# mother.net
KiCad netlist of a schematic drawn in EAGLE
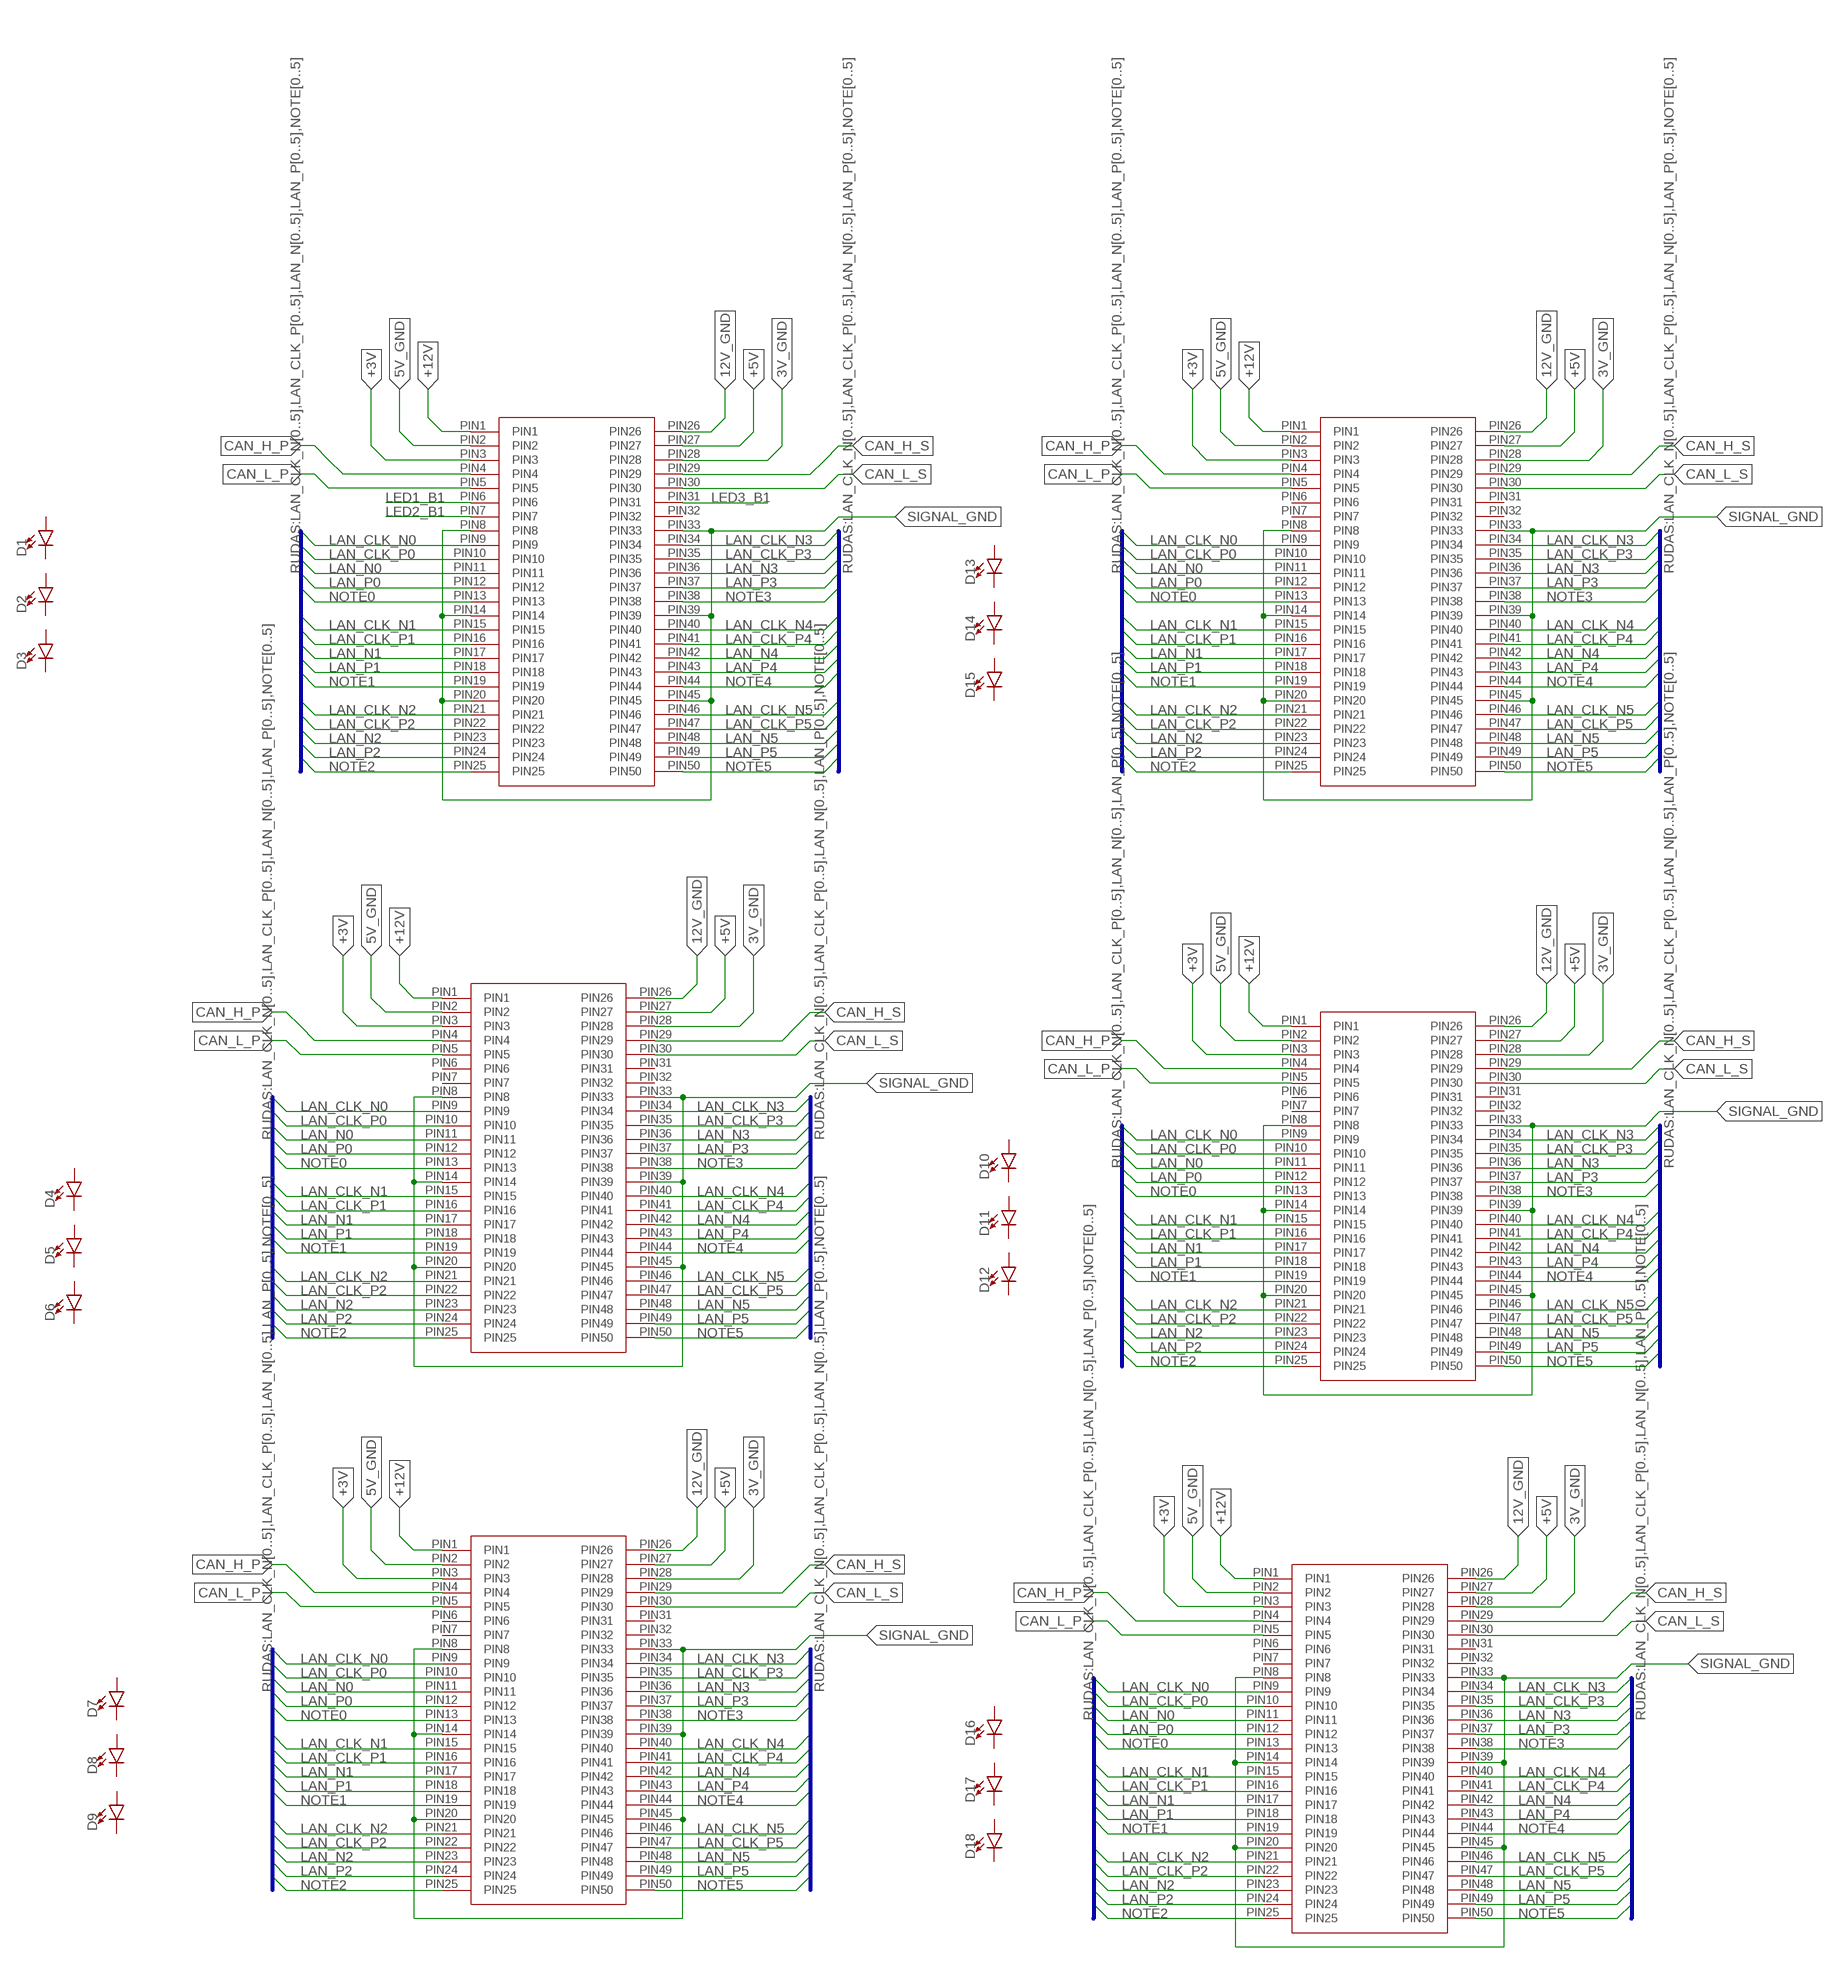
[diagram p0: schematic, sheet 1]

(export (version "E")
  (design (tool "Eeschema 10.0.6"))
  (components
    (comp (ref "D1")
      (value "LED-FKIT-1206")
      (footprint "eagle-import:FKIT-LED-1206")
      (libsource (lib "eagle-import") (part "LED-FKIT-1206"))
    )
    (comp (ref "D2")
      (value "LED-FKIT-1206")
      (footprint "eagle-import:FKIT-LED-1206")
      (libsource (lib "eagle-import") (part "LED-FKIT-1206"))
    )
    (comp (ref "D3")
      (value "LED-FKIT-1206")
      (footprint "eagle-import:FKIT-LED-1206")
      (libsource (lib "eagle-import") (part "LED-FKIT-1206"))
    )
    (comp (ref "D4")
      (value "LED-FKIT-1206")
      (footprint "eagle-import:FKIT-LED-1206")
      (libsource (lib "eagle-import") (part "LED-FKIT-1206"))
    )
    (comp (ref "D5")
      (value "LED-FKIT-1206")
      (footprint "eagle-import:FKIT-LED-1206")
      (libsource (lib "eagle-import") (part "LED-FKIT-1206"))
    )
    (comp (ref "D6")
      (value "LED-FKIT-1206")
      (footprint "eagle-import:FKIT-LED-1206")
      (libsource (lib "eagle-import") (part "LED-FKIT-1206"))
    )
    (comp (ref "D7")
      (value "LED-FKIT-1206")
      (footprint "eagle-import:FKIT-LED-1206")
      (libsource (lib "eagle-import") (part "LED-FKIT-1206"))
    )
    (comp (ref "D8")
      (value "LED-FKIT-1206")
      (footprint "eagle-import:FKIT-LED-1206")
      (libsource (lib "eagle-import") (part "LED-FKIT-1206"))
    )
    (comp (ref "D9")
      (value "LED-FKIT-1206")
      (footprint "eagle-import:FKIT-LED-1206")
      (libsource (lib "eagle-import") (part "LED-FKIT-1206"))
    )
    (comp (ref "D10")
      (value "LED-FKIT-1206")
      (footprint "eagle-import:FKIT-LED-1206")
      (libsource (lib "eagle-import") (part "LED-FKIT-1206"))
    )
    (comp (ref "D11")
      (value "LED-FKIT-1206")
      (footprint "eagle-import:FKIT-LED-1206")
      (libsource (lib "eagle-import") (part "LED-FKIT-1206"))
    )
    (comp (ref "D12")
      (value "LED-FKIT-1206")
      (footprint "eagle-import:FKIT-LED-1206")
      (libsource (lib "eagle-import") (part "LED-FKIT-1206"))
    )
    (comp (ref "D13")
      (value "LED-FKIT-1206")
      (footprint "eagle-import:FKIT-LED-1206")
      (libsource (lib "eagle-import") (part "LED-FKIT-1206"))
    )
    (comp (ref "D14")
      (value "LED-FKIT-1206")
      (footprint "eagle-import:FKIT-LED-1206")
      (libsource (lib "eagle-import") (part "LED-FKIT-1206"))
    )
    (comp (ref "D15")
      (value "LED-FKIT-1206")
      (footprint "eagle-import:FKIT-LED-1206")
      (libsource (lib "eagle-import") (part "LED-FKIT-1206"))
    )
    (comp (ref "D16")
      (value "LED-FKIT-1206")
      (footprint "eagle-import:FKIT-LED-1206")
      (libsource (lib "eagle-import") (part "LED-FKIT-1206"))
    )
    (comp (ref "D17")
      (value "LED-FKIT-1206")
      (footprint "eagle-import:FKIT-LED-1206")
      (libsource (lib "eagle-import") (part "LED-FKIT-1206"))
    )
    (comp (ref "D18")
      (value "LED-FKIT-1206")
      (footprint "eagle-import:FKIT-LED-1206")
      (libsource (lib "eagle-import") (part "LED-FKIT-1206"))
    )
    (comp (ref "U$1")
      (value "CARD_EDGE_50PINM80-4115042")
      (footprint "eagle-import:M80-4115042")
      (libsource (lib "eagle-import") (part "CARD_EDGE_50PINM80-4115042"))
    )
    (comp (ref "U$2")
      (value "CARD_EDGE_50PINM80-4115042")
      (footprint "eagle-import:M80-4115042")
      (libsource (lib "eagle-import") (part "CARD_EDGE_50PINM80-4115042"))
    )
    (comp (ref "U$3")
      (value "CARD_EDGE_50PINM80-4115042")
      (footprint "eagle-import:M80-4115042")
      (libsource (lib "eagle-import") (part "CARD_EDGE_50PINM80-4115042"))
    )
    (comp (ref "U$4")
      (value "CARD_EDGE_50PINM80-4115042")
      (footprint "eagle-import:M80-4115042")
      (libsource (lib "eagle-import") (part "CARD_EDGE_50PINM80-4115042"))
    )
    (comp (ref "U$5")
      (value "CARD_EDGE_50PINM80-4115042")
      (footprint "eagle-import:M80-4115042")
      (libsource (lib "eagle-import") (part "CARD_EDGE_50PINM80-4115042"))
    )
    (comp (ref "U$6")
      (value "CARD_EDGE_50PINM80-4115042")
      (footprint "eagle-import:M80-4115042")
      (libsource (lib "eagle-import") (part "CARD_EDGE_50PINM80-4115042"))
    )
  )
  (nets
    (net (code "1") (name "+3V") (class "Default")
      (node (ref "U$1") (pin "PIN3") (pinfunction "PIN3_PIN3") (pintype "bidirectional"))
      (node (ref "U$2") (pin "PIN3") (pinfunction "PIN3_PIN3") (pintype "bidirectional"))
      (node (ref "U$3") (pin "PIN3") (pinfunction "PIN3_PIN3") (pintype "bidirectional"))
      (node (ref "U$4") (pin "PIN3") (pinfunction "PIN3_PIN3") (pintype "bidirectional"))
      (node (ref "U$5") (pin "PIN3") (pinfunction "PIN3_PIN3") (pintype "bidirectional"))
      (node (ref "U$6") (pin "PIN3") (pinfunction "PIN3_PIN3") (pintype "bidirectional"))
    )
    (net (code "2") (name "+5V") (class "Default")
      (node (ref "U$1") (pin "PIN27") (pinfunction "PIN27_PIN27") (pintype "bidirectional"))
      (node (ref "U$2") (pin "PIN27") (pinfunction "PIN27_PIN27") (pintype "bidirectional"))
      (node (ref "U$3") (pin "PIN27") (pinfunction "PIN27_PIN27") (pintype "bidirectional"))
      (node (ref "U$4") (pin "PIN27") (pinfunction "PIN27_PIN27") (pintype "bidirectional"))
      (node (ref "U$5") (pin "PIN27") (pinfunction "PIN27_PIN27") (pintype "bidirectional"))
      (node (ref "U$6") (pin "PIN27") (pinfunction "PIN27_PIN27") (pintype "bidirectional"))
    )
    (net (code "3") (name "+12V") (class "Default")
      (node (ref "U$1") (pin "PIN1") (pinfunction "PIN1_PIN1") (pintype "bidirectional"))
      (node (ref "U$2") (pin "PIN1") (pinfunction "PIN1_PIN1") (pintype "bidirectional"))
      (node (ref "U$3") (pin "PIN1") (pinfunction "PIN1_PIN1") (pintype "bidirectional"))
      (node (ref "U$4") (pin "PIN1") (pinfunction "PIN1_PIN1") (pintype "bidirectional"))
      (node (ref "U$5") (pin "PIN1") (pinfunction "PIN1_PIN1") (pintype "bidirectional"))
      (node (ref "U$6") (pin "PIN1") (pinfunction "PIN1_PIN1") (pintype "bidirectional"))
    )
    (net (code "4") (name "/LAN_CLK_N0") (class "Default")
      (node (ref "U$1") (pin "PIN9") (pinfunction "PIN9_PIN9") (pintype "bidirectional"))
      (node (ref "U$2") (pin "PIN9") (pinfunction "PIN9_PIN9") (pintype "bidirectional"))
      (node (ref "U$3") (pin "PIN9") (pinfunction "PIN9_PIN9") (pintype "bidirectional"))
      (node (ref "U$4") (pin "PIN9") (pinfunction "PIN9_PIN9") (pintype "bidirectional"))
      (node (ref "U$5") (pin "PIN9") (pinfunction "PIN9_PIN9") (pintype "bidirectional"))
      (node (ref "U$6") (pin "PIN9") (pinfunction "PIN9_PIN9") (pintype "bidirectional"))
    )
    (net (code "5") (name "/LAN_CLK_N1") (class "Default")
      (node (ref "U$1") (pin "PIN15") (pinfunction "PIN15_PIN15") (pintype "bidirectional"))
      (node (ref "U$2") (pin "PIN15") (pinfunction "PIN15_PIN15") (pintype "bidirectional"))
      (node (ref "U$3") (pin "PIN15") (pinfunction "PIN15_PIN15") (pintype "bidirectional"))
      (node (ref "U$4") (pin "PIN15") (pinfunction "PIN15_PIN15") (pintype "bidirectional"))
      (node (ref "U$5") (pin "PIN15") (pinfunction "PIN15_PIN15") (pintype "bidirectional"))
      (node (ref "U$6") (pin "PIN15") (pinfunction "PIN15_PIN15") (pintype "bidirectional"))
    )
    (net (code "6") (name "/LAN_CLK_N2") (class "Default")
      (node (ref "U$1") (pin "PIN21") (pinfunction "PIN21_PIN21") (pintype "bidirectional"))
      (node (ref "U$2") (pin "PIN21") (pinfunction "PIN21_PIN21") (pintype "bidirectional"))
      (node (ref "U$3") (pin "PIN21") (pinfunction "PIN21_PIN21") (pintype "bidirectional"))
      (node (ref "U$4") (pin "PIN21") (pinfunction "PIN21_PIN21") (pintype "bidirectional"))
      (node (ref "U$5") (pin "PIN21") (pinfunction "PIN21_PIN21") (pintype "bidirectional"))
      (node (ref "U$6") (pin "PIN21") (pinfunction "PIN21_PIN21") (pintype "bidirectional"))
    )
    (net (code "7") (name "/LAN_CLK_N3") (class "Default")
      (node (ref "U$1") (pin "PIN34") (pinfunction "PIN34_PIN34") (pintype "bidirectional"))
      (node (ref "U$2") (pin "PIN34") (pinfunction "PIN34_PIN34") (pintype "bidirectional"))
      (node (ref "U$3") (pin "PIN34") (pinfunction "PIN34_PIN34") (pintype "bidirectional"))
      (node (ref "U$4") (pin "PIN34") (pinfunction "PIN34_PIN34") (pintype "bidirectional"))
      (node (ref "U$5") (pin "PIN34") (pinfunction "PIN34_PIN34") (pintype "bidirectional"))
      (node (ref "U$6") (pin "PIN34") (pinfunction "PIN34_PIN34") (pintype "bidirectional"))
    )
    (net (code "8") (name "/LAN_CLK_N4") (class "Default")
      (node (ref "U$1") (pin "PIN40") (pinfunction "PIN40_PIN40") (pintype "bidirectional"))
      (node (ref "U$2") (pin "PIN40") (pinfunction "PIN40_PIN40") (pintype "bidirectional"))
      (node (ref "U$3") (pin "PIN40") (pinfunction "PIN40_PIN40") (pintype "bidirectional"))
      (node (ref "U$4") (pin "PIN40") (pinfunction "PIN40_PIN40") (pintype "bidirectional"))
      (node (ref "U$5") (pin "PIN40") (pinfunction "PIN40_PIN40") (pintype "bidirectional"))
      (node (ref "U$6") (pin "PIN40") (pinfunction "PIN40_PIN40") (pintype "bidirectional"))
    )
    (net (code "9") (name "/LAN_CLK_N5") (class "Default")
      (node (ref "U$1") (pin "PIN46") (pinfunction "PIN46_PIN46") (pintype "bidirectional"))
      (node (ref "U$2") (pin "PIN46") (pinfunction "PIN46_PIN46") (pintype "bidirectional"))
      (node (ref "U$3") (pin "PIN46") (pinfunction "PIN46_PIN46") (pintype "bidirectional"))
      (node (ref "U$4") (pin "PIN46") (pinfunction "PIN46_PIN46") (pintype "bidirectional"))
      (node (ref "U$5") (pin "PIN46") (pinfunction "PIN46_PIN46") (pintype "bidirectional"))
      (node (ref "U$6") (pin "PIN46") (pinfunction "PIN46_PIN46") (pintype "bidirectional"))
    )
    (net (code "10") (name "/LAN_CLK_P0") (class "Default")
      (node (ref "U$1") (pin "PIN10") (pinfunction "PIN10_PIN10") (pintype "bidirectional"))
      (node (ref "U$2") (pin "PIN10") (pinfunction "PIN10_PIN10") (pintype "bidirectional"))
      (node (ref "U$3") (pin "PIN10") (pinfunction "PIN10_PIN10") (pintype "bidirectional"))
      (node (ref "U$4") (pin "PIN10") (pinfunction "PIN10_PIN10") (pintype "bidirectional"))
      (node (ref "U$5") (pin "PIN10") (pinfunction "PIN10_PIN10") (pintype "bidirectional"))
      (node (ref "U$6") (pin "PIN10") (pinfunction "PIN10_PIN10") (pintype "bidirectional"))
    )
    (net (code "11") (name "/LAN_CLK_P1") (class "Default")
      (node (ref "U$1") (pin "PIN16") (pinfunction "PIN16_PIN16") (pintype "bidirectional"))
      (node (ref "U$2") (pin "PIN16") (pinfunction "PIN16_PIN16") (pintype "bidirectional"))
      (node (ref "U$3") (pin "PIN16") (pinfunction "PIN16_PIN16") (pintype "bidirectional"))
      (node (ref "U$4") (pin "PIN16") (pinfunction "PIN16_PIN16") (pintype "bidirectional"))
      (node (ref "U$5") (pin "PIN16") (pinfunction "PIN16_PIN16") (pintype "bidirectional"))
      (node (ref "U$6") (pin "PIN16") (pinfunction "PIN16_PIN16") (pintype "bidirectional"))
    )
    (net (code "12") (name "/LAN_CLK_P2") (class "Default")
      (node (ref "U$1") (pin "PIN22") (pinfunction "PIN22_PIN22") (pintype "bidirectional"))
      (node (ref "U$2") (pin "PIN22") (pinfunction "PIN22_PIN22") (pintype "bidirectional"))
      (node (ref "U$3") (pin "PIN22") (pinfunction "PIN22_PIN22") (pintype "bidirectional"))
      (node (ref "U$4") (pin "PIN22") (pinfunction "PIN22_PIN22") (pintype "bidirectional"))
      (node (ref "U$5") (pin "PIN22") (pinfunction "PIN22_PIN22") (pintype "bidirectional"))
      (node (ref "U$6") (pin "PIN22") (pinfunction "PIN22_PIN22") (pintype "bidirectional"))
    )
    (net (code "13") (name "/LAN_CLK_P3") (class "Default")
      (node (ref "U$1") (pin "PIN35") (pinfunction "PIN35_PIN35") (pintype "bidirectional"))
      (node (ref "U$2") (pin "PIN35") (pinfunction "PIN35_PIN35") (pintype "bidirectional"))
      (node (ref "U$3") (pin "PIN35") (pinfunction "PIN35_PIN35") (pintype "bidirectional"))
      (node (ref "U$4") (pin "PIN35") (pinfunction "PIN35_PIN35") (pintype "bidirectional"))
      (node (ref "U$5") (pin "PIN35") (pinfunction "PIN35_PIN35") (pintype "bidirectional"))
      (node (ref "U$6") (pin "PIN35") (pinfunction "PIN35_PIN35") (pintype "bidirectional"))
    )
    (net (code "14") (name "/LAN_CLK_P4") (class "Default")
      (node (ref "U$1") (pin "PIN41") (pinfunction "PIN41_PIN41") (pintype "bidirectional"))
      (node (ref "U$2") (pin "PIN41") (pinfunction "PIN41_PIN41") (pintype "bidirectional"))
      (node (ref "U$3") (pin "PIN41") (pinfunction "PIN41_PIN41") (pintype "bidirectional"))
      (node (ref "U$4") (pin "PIN41") (pinfunction "PIN41_PIN41") (pintype "bidirectional"))
      (node (ref "U$5") (pin "PIN41") (pinfunction "PIN41_PIN41") (pintype "bidirectional"))
      (node (ref "U$6") (pin "PIN41") (pinfunction "PIN41_PIN41") (pintype "bidirectional"))
    )
    (net (code "15") (name "/LAN_CLK_P5") (class "Default")
      (node (ref "U$1") (pin "PIN47") (pinfunction "PIN47_PIN47") (pintype "bidirectional"))
      (node (ref "U$2") (pin "PIN47") (pinfunction "PIN47_PIN47") (pintype "bidirectional"))
      (node (ref "U$3") (pin "PIN47") (pinfunction "PIN47_PIN47") (pintype "bidirectional"))
      (node (ref "U$4") (pin "PIN47") (pinfunction "PIN47_PIN47") (pintype "bidirectional"))
      (node (ref "U$5") (pin "PIN47") (pinfunction "PIN47_PIN47") (pintype "bidirectional"))
      (node (ref "U$6") (pin "PIN47") (pinfunction "PIN47_PIN47") (pintype "bidirectional"))
    )
    (net (code "16") (name "/LAN_N0") (class "Default")
      (node (ref "U$1") (pin "PIN11") (pinfunction "PIN11_PIN11") (pintype "bidirectional"))
      (node (ref "U$2") (pin "PIN11") (pinfunction "PIN11_PIN11") (pintype "bidirectional"))
      (node (ref "U$3") (pin "PIN11") (pinfunction "PIN11_PIN11") (pintype "bidirectional"))
      (node (ref "U$4") (pin "PIN11") (pinfunction "PIN11_PIN11") (pintype "bidirectional"))
      (node (ref "U$5") (pin "PIN11") (pinfunction "PIN11_PIN11") (pintype "bidirectional"))
      (node (ref "U$6") (pin "PIN11") (pinfunction "PIN11_PIN11") (pintype "bidirectional"))
    )
    (net (code "17") (name "/LAN_N1") (class "Default")
      (node (ref "U$1") (pin "PIN17") (pinfunction "PIN17_PIN17") (pintype "bidirectional"))
      (node (ref "U$2") (pin "PIN17") (pinfunction "PIN17_PIN17") (pintype "bidirectional"))
      (node (ref "U$3") (pin "PIN17") (pinfunction "PIN17_PIN17") (pintype "bidirectional"))
      (node (ref "U$4") (pin "PIN17") (pinfunction "PIN17_PIN17") (pintype "bidirectional"))
      (node (ref "U$5") (pin "PIN17") (pinfunction "PIN17_PIN17") (pintype "bidirectional"))
      (node (ref "U$6") (pin "PIN17") (pinfunction "PIN17_PIN17") (pintype "bidirectional"))
    )
    (net (code "18") (name "/LAN_N2") (class "Default")
      (node (ref "U$1") (pin "PIN23") (pinfunction "PIN23_PIN23") (pintype "bidirectional"))
      (node (ref "U$2") (pin "PIN23") (pinfunction "PIN23_PIN23") (pintype "bidirectional"))
      (node (ref "U$3") (pin "PIN23") (pinfunction "PIN23_PIN23") (pintype "bidirectional"))
      (node (ref "U$4") (pin "PIN23") (pinfunction "PIN23_PIN23") (pintype "bidirectional"))
      (node (ref "U$5") (pin "PIN23") (pinfunction "PIN23_PIN23") (pintype "bidirectional"))
      (node (ref "U$6") (pin "PIN23") (pinfunction "PIN23_PIN23") (pintype "bidirectional"))
    )
    (net (code "19") (name "/LAN_N3") (class "Default")
      (node (ref "U$1") (pin "PIN36") (pinfunction "PIN36_PIN36") (pintype "bidirectional"))
      (node (ref "U$2") (pin "PIN36") (pinfunction "PIN36_PIN36") (pintype "bidirectional"))
      (node (ref "U$3") (pin "PIN36") (pinfunction "PIN36_PIN36") (pintype "bidirectional"))
      (node (ref "U$4") (pin "PIN36") (pinfunction "PIN36_PIN36") (pintype "bidirectional"))
      (node (ref "U$5") (pin "PIN36") (pinfunction "PIN36_PIN36") (pintype "bidirectional"))
      (node (ref "U$6") (pin "PIN36") (pinfunction "PIN36_PIN36") (pintype "bidirectional"))
    )
    (net (code "20") (name "/LAN_N4") (class "Default")
      (node (ref "U$1") (pin "PIN42") (pinfunction "PIN42_PIN42") (pintype "bidirectional"))
      (node (ref "U$2") (pin "PIN42") (pinfunction "PIN42_PIN42") (pintype "bidirectional"))
      (node (ref "U$3") (pin "PIN42") (pinfunction "PIN42_PIN42") (pintype "bidirectional"))
      (node (ref "U$4") (pin "PIN42") (pinfunction "PIN42_PIN42") (pintype "bidirectional"))
      (node (ref "U$5") (pin "PIN42") (pinfunction "PIN42_PIN42") (pintype "bidirectional"))
      (node (ref "U$6") (pin "PIN42") (pinfunction "PIN42_PIN42") (pintype "bidirectional"))
    )
    (net (code "21") (name "/LAN_N5") (class "Default")
      (node (ref "U$1") (pin "PIN48") (pinfunction "PIN48_PIN48") (pintype "bidirectional"))
      (node (ref "U$2") (pin "PIN48") (pinfunction "PIN48_PIN48") (pintype "bidirectional"))
      (node (ref "U$3") (pin "PIN48") (pinfunction "PIN48_PIN48") (pintype "bidirectional"))
      (node (ref "U$4") (pin "PIN48") (pinfunction "PIN48_PIN48") (pintype "bidirectional"))
      (node (ref "U$5") (pin "PIN48") (pinfunction "PIN48_PIN48") (pintype "bidirectional"))
      (node (ref "U$6") (pin "PIN48") (pinfunction "PIN48_PIN48") (pintype "bidirectional"))
    )
    (net (code "22") (name "/LAN_P0") (class "Default")
      (node (ref "U$1") (pin "PIN12") (pinfunction "PIN12_PIN12") (pintype "bidirectional"))
      (node (ref "U$2") (pin "PIN12") (pinfunction "PIN12_PIN12") (pintype "bidirectional"))
      (node (ref "U$3") (pin "PIN12") (pinfunction "PIN12_PIN12") (pintype "bidirectional"))
      (node (ref "U$4") (pin "PIN12") (pinfunction "PIN12_PIN12") (pintype "bidirectional"))
      (node (ref "U$5") (pin "PIN12") (pinfunction "PIN12_PIN12") (pintype "bidirectional"))
      (node (ref "U$6") (pin "PIN12") (pinfunction "PIN12_PIN12") (pintype "bidirectional"))
    )
    (net (code "23") (name "/LAN_P1") (class "Default")
      (node (ref "U$1") (pin "PIN18") (pinfunction "PIN18_PIN18") (pintype "bidirectional"))
      (node (ref "U$2") (pin "PIN18") (pinfunction "PIN18_PIN18") (pintype "bidirectional"))
      (node (ref "U$3") (pin "PIN18") (pinfunction "PIN18_PIN18") (pintype "bidirectional"))
      (node (ref "U$4") (pin "PIN18") (pinfunction "PIN18_PIN18") (pintype "bidirectional"))
      (node (ref "U$5") (pin "PIN18") (pinfunction "PIN18_PIN18") (pintype "bidirectional"))
      (node (ref "U$6") (pin "PIN18") (pinfunction "PIN18_PIN18") (pintype "bidirectional"))
    )
    (net (code "24") (name "/LAN_P2") (class "Default")
      (node (ref "U$1") (pin "PIN24") (pinfunction "PIN24_PIN24") (pintype "bidirectional"))
      (node (ref "U$2") (pin "PIN24") (pinfunction "PIN24_PIN24") (pintype "bidirectional"))
      (node (ref "U$3") (pin "PIN24") (pinfunction "PIN24_PIN24") (pintype "bidirectional"))
      (node (ref "U$4") (pin "PIN24") (pinfunction "PIN24_PIN24") (pintype "bidirectional"))
      (node (ref "U$5") (pin "PIN24") (pinfunction "PIN24_PIN24") (pintype "bidirectional"))
      (node (ref "U$6") (pin "PIN24") (pinfunction "PIN24_PIN24") (pintype "bidirectional"))
    )
    (net (code "25") (name "/LAN_P3") (class "Default")
      (node (ref "U$1") (pin "PIN37") (pinfunction "PIN37_PIN37") (pintype "bidirectional"))
      (node (ref "U$2") (pin "PIN37") (pinfunction "PIN37_PIN37") (pintype "bidirectional"))
      (node (ref "U$3") (pin "PIN37") (pinfunction "PIN37_PIN37") (pintype "bidirectional"))
      (node (ref "U$4") (pin "PIN37") (pinfunction "PIN37_PIN37") (pintype "bidirectional"))
      (node (ref "U$5") (pin "PIN37") (pinfunction "PIN37_PIN37") (pintype "bidirectional"))
      (node (ref "U$6") (pin "PIN37") (pinfunction "PIN37_PIN37") (pintype "bidirectional"))
    )
    (net (code "26") (name "/LAN_P4") (class "Default")
      (node (ref "U$1") (pin "PIN43") (pinfunction "PIN43_PIN43") (pintype "bidirectional"))
      (node (ref "U$2") (pin "PIN43") (pinfunction "PIN43_PIN43") (pintype "bidirectional"))
      (node (ref "U$3") (pin "PIN43") (pinfunction "PIN43_PIN43") (pintype "bidirectional"))
      (node (ref "U$4") (pin "PIN43") (pinfunction "PIN43_PIN43") (pintype "bidirectional"))
      (node (ref "U$5") (pin "PIN43") (pinfunction "PIN43_PIN43") (pintype "bidirectional"))
      (node (ref "U$6") (pin "PIN43") (pinfunction "PIN43_PIN43") (pintype "bidirectional"))
    )
    (net (code "27") (name "/LAN_P5") (class "Default")
      (node (ref "U$1") (pin "PIN49") (pinfunction "PIN49_PIN49") (pintype "bidirectional"))
      (node (ref "U$2") (pin "PIN49") (pinfunction "PIN49_PIN49") (pintype "bidirectional"))
      (node (ref "U$3") (pin "PIN49") (pinfunction "PIN49_PIN49") (pintype "bidirectional"))
      (node (ref "U$4") (pin "PIN49") (pinfunction "PIN49_PIN49") (pintype "bidirectional"))
      (node (ref "U$5") (pin "PIN49") (pinfunction "PIN49_PIN49") (pintype "bidirectional"))
      (node (ref "U$6") (pin "PIN49") (pinfunction "PIN49_PIN49") (pintype "bidirectional"))
    )
    (net (code "28") (name "/LED1_B1") (class "Default")
      (node (ref "U$5") (pin "PIN6") (pinfunction "PIN6_PIN6") (pintype "bidirectional"))
    )
    (net (code "29") (name "/LED2_B1") (class "Default")
      (node (ref "U$5") (pin "PIN7") (pinfunction "PIN7_PIN7") (pintype "bidirectional"))
    )
    (net (code "30") (name "/LED3_B1") (class "Default")
      (node (ref "U$5") (pin "PIN31") (pinfunction "PIN31_PIN31") (pintype "bidirectional"))
    )
    (net (code "31") (name "/NOTE0") (class "Default")
      (node (ref "U$1") (pin "PIN13") (pinfunction "PIN13_PIN13") (pintype "bidirectional"))
      (node (ref "U$2") (pin "PIN13") (pinfunction "PIN13_PIN13") (pintype "bidirectional"))
      (node (ref "U$3") (pin "PIN13") (pinfunction "PIN13_PIN13") (pintype "bidirectional"))
      (node (ref "U$4") (pin "PIN13") (pinfunction "PIN13_PIN13") (pintype "bidirectional"))
      (node (ref "U$5") (pin "PIN13") (pinfunction "PIN13_PIN13") (pintype "bidirectional"))
      (node (ref "U$6") (pin "PIN13") (pinfunction "PIN13_PIN13") (pintype "bidirectional"))
    )
    (net (code "32") (name "/NOTE1") (class "Default")
      (node (ref "U$1") (pin "PIN19") (pinfunction "PIN19_PIN19") (pintype "bidirectional"))
      (node (ref "U$2") (pin "PIN19") (pinfunction "PIN19_PIN19") (pintype "bidirectional"))
      (node (ref "U$3") (pin "PIN19") (pinfunction "PIN19_PIN19") (pintype "bidirectional"))
      (node (ref "U$4") (pin "PIN19") (pinfunction "PIN19_PIN19") (pintype "bidirectional"))
      (node (ref "U$5") (pin "PIN19") (pinfunction "PIN19_PIN19") (pintype "bidirectional"))
      (node (ref "U$6") (pin "PIN19") (pinfunction "PIN19_PIN19") (pintype "bidirectional"))
    )
    (net (code "33") (name "/NOTE2") (class "Default")
      (node (ref "U$1") (pin "PIN25") (pinfunction "PIN25_PIN25") (pintype "bidirectional"))
      (node (ref "U$2") (pin "PIN25") (pinfunction "PIN25_PIN25") (pintype "bidirectional"))
      (node (ref "U$3") (pin "PIN25") (pinfunction "PIN25_PIN25") (pintype "bidirectional"))
      (node (ref "U$4") (pin "PIN25") (pinfunction "PIN25_PIN25") (pintype "bidirectional"))
      (node (ref "U$5") (pin "PIN25") (pinfunction "PIN25_PIN25") (pintype "bidirectional"))
      (node (ref "U$6") (pin "PIN25") (pinfunction "PIN25_PIN25") (pintype "bidirectional"))
    )
    (net (code "34") (name "/NOTE3") (class "Default")
      (node (ref "U$1") (pin "PIN38") (pinfunction "PIN38_PIN38") (pintype "bidirectional"))
      (node (ref "U$2") (pin "PIN38") (pinfunction "PIN38_PIN38") (pintype "bidirectional"))
      (node (ref "U$3") (pin "PIN38") (pinfunction "PIN38_PIN38") (pintype "bidirectional"))
      (node (ref "U$4") (pin "PIN38") (pinfunction "PIN38_PIN38") (pintype "bidirectional"))
      (node (ref "U$5") (pin "PIN38") (pinfunction "PIN38_PIN38") (pintype "bidirectional"))
      (node (ref "U$6") (pin "PIN38") (pinfunction "PIN38_PIN38") (pintype "bidirectional"))
    )
    (net (code "35") (name "/NOTE4") (class "Default")
      (node (ref "U$1") (pin "PIN44") (pinfunction "PIN44_PIN44") (pintype "bidirectional"))
      (node (ref "U$2") (pin "PIN44") (pinfunction "PIN44_PIN44") (pintype "bidirectional"))
      (node (ref "U$3") (pin "PIN44") (pinfunction "PIN44_PIN44") (pintype "bidirectional"))
      (node (ref "U$4") (pin "PIN44") (pinfunction "PIN44_PIN44") (pintype "bidirectional"))
      (node (ref "U$5") (pin "PIN44") (pinfunction "PIN44_PIN44") (pintype "bidirectional"))
      (node (ref "U$6") (pin "PIN44") (pinfunction "PIN44_PIN44") (pintype "bidirectional"))
    )
    (net (code "36") (name "/NOTE5") (class "Default")
      (node (ref "U$1") (pin "PIN50") (pinfunction "PIN50_PIN50") (pintype "bidirectional"))
      (node (ref "U$2") (pin "PIN50") (pinfunction "PIN50_PIN50") (pintype "bidirectional"))
      (node (ref "U$3") (pin "PIN50") (pinfunction "PIN50_PIN50") (pintype "bidirectional"))
      (node (ref "U$4") (pin "PIN50") (pinfunction "PIN50_PIN50") (pintype "bidirectional"))
      (node (ref "U$5") (pin "PIN50") (pinfunction "PIN50_PIN50") (pintype "bidirectional"))
      (node (ref "U$6") (pin "PIN50") (pinfunction "PIN50_PIN50") (pintype "bidirectional"))
    )
    (net (code "38") (name "3V_GND") (class "Default")
      (node (ref "U$1") (pin "PIN28") (pinfunction "PIN28_PIN28") (pintype "bidirectional"))
      (node (ref "U$2") (pin "PIN28") (pinfunction "PIN28_PIN28") (pintype "bidirectional"))
      (node (ref "U$3") (pin "PIN28") (pinfunction "PIN28_PIN28") (pintype "bidirectional"))
      (node (ref "U$4") (pin "PIN28") (pinfunction "PIN28_PIN28") (pintype "bidirectional"))
      (node (ref "U$5") (pin "PIN28") (pinfunction "PIN28_PIN28") (pintype "bidirectional"))
      (node (ref "U$6") (pin "PIN28") (pinfunction "PIN28_PIN28") (pintype "bidirectional"))
    )
    (net (code "39") (name "5V_GND") (class "Default")
      (node (ref "U$1") (pin "PIN2") (pinfunction "PIN2_PIN2") (pintype "bidirectional"))
      (node (ref "U$2") (pin "PIN2") (pinfunction "PIN2_PIN2") (pintype "bidirectional"))
      (node (ref "U$3") (pin "PIN2") (pinfunction "PIN2_PIN2") (pintype "bidirectional"))
      (node (ref "U$4") (pin "PIN2") (pinfunction "PIN2_PIN2") (pintype "bidirectional"))
      (node (ref "U$5") (pin "PIN2") (pinfunction "PIN2_PIN2") (pintype "bidirectional"))
      (node (ref "U$6") (pin "PIN2") (pinfunction "PIN2_PIN2") (pintype "bidirectional"))
    )
    (net (code "40") (name "12V_GND") (class "Default")
      (node (ref "U$1") (pin "PIN26") (pinfunction "PIN26_PIN26") (pintype "bidirectional"))
      (node (ref "U$2") (pin "PIN26") (pinfunction "PIN26_PIN26") (pintype "bidirectional"))
      (node (ref "U$3") (pin "PIN26") (pinfunction "PIN26_PIN26") (pintype "bidirectional"))
      (node (ref "U$4") (pin "PIN26") (pinfunction "PIN26_PIN26") (pintype "bidirectional"))
      (node (ref "U$5") (pin "PIN26") (pinfunction "PIN26_PIN26") (pintype "bidirectional"))
      (node (ref "U$6") (pin "PIN26") (pinfunction "PIN26_PIN26") (pintype "bidirectional"))
    )
    (net (code "41") (name "CAN_H_P") (class "Default")
      (node (ref "U$1") (pin "PIN4") (pinfunction "PIN4_PIN4") (pintype "bidirectional"))
      (node (ref "U$2") (pin "PIN4") (pinfunction "PIN4_PIN4") (pintype "bidirectional"))
      (node (ref "U$3") (pin "PIN4") (pinfunction "PIN4_PIN4") (pintype "bidirectional"))
      (node (ref "U$4") (pin "PIN4") (pinfunction "PIN4_PIN4") (pintype "bidirectional"))
      (node (ref "U$5") (pin "PIN4") (pinfunction "PIN4_PIN4") (pintype "bidirectional"))
      (node (ref "U$6") (pin "PIN4") (pinfunction "PIN4_PIN4") (pintype "bidirectional"))
    )
    (net (code "42") (name "CAN_H_S") (class "Default")
      (node (ref "U$1") (pin "PIN29") (pinfunction "PIN29_PIN29") (pintype "bidirectional"))
      (node (ref "U$2") (pin "PIN29") (pinfunction "PIN29_PIN29") (pintype "bidirectional"))
      (node (ref "U$3") (pin "PIN29") (pinfunction "PIN29_PIN29") (pintype "bidirectional"))
      (node (ref "U$4") (pin "PIN29") (pinfunction "PIN29_PIN29") (pintype "bidirectional"))
      (node (ref "U$5") (pin "PIN29") (pinfunction "PIN29_PIN29") (pintype "bidirectional"))
      (node (ref "U$6") (pin "PIN29") (pinfunction "PIN29_PIN29") (pintype "bidirectional"))
    )
    (net (code "43") (name "CAN_L_P") (class "Default")
      (node (ref "U$1") (pin "PIN5") (pinfunction "PIN5_PIN5") (pintype "bidirectional"))
      (node (ref "U$2") (pin "PIN5") (pinfunction "PIN5_PIN5") (pintype "bidirectional"))
      (node (ref "U$3") (pin "PIN5") (pinfunction "PIN5_PIN5") (pintype "bidirectional"))
      (node (ref "U$4") (pin "PIN5") (pinfunction "PIN5_PIN5") (pintype "bidirectional"))
      (node (ref "U$5") (pin "PIN5") (pinfunction "PIN5_PIN5") (pintype "bidirectional"))
      (node (ref "U$6") (pin "PIN5") (pinfunction "PIN5_PIN5") (pintype "bidirectional"))
    )
    (net (code "44") (name "CAN_L_S") (class "Default")
      (node (ref "U$1") (pin "PIN30") (pinfunction "PIN30_PIN30") (pintype "bidirectional"))
      (node (ref "U$2") (pin "PIN30") (pinfunction "PIN30_PIN30") (pintype "bidirectional"))
      (node (ref "U$3") (pin "PIN30") (pinfunction "PIN30_PIN30") (pintype "bidirectional"))
      (node (ref "U$4") (pin "PIN30") (pinfunction "PIN30_PIN30") (pintype "bidirectional"))
      (node (ref "U$5") (pin "PIN30") (pinfunction "PIN30_PIN30") (pintype "bidirectional"))
      (node (ref "U$6") (pin "PIN30") (pinfunction "PIN30_PIN30") (pintype "bidirectional"))
    )
    (net (code "45") (name "SIGNAL_GND") (class "Default")
      (node (ref "U$1") (pin "PIN14") (pinfunction "PIN14_PIN14") (pintype "bidirectional"))
      (node (ref "U$1") (pin "PIN20") (pinfunction "PIN20_PIN20") (pintype "bidirectional"))
      (node (ref "U$1") (pin "PIN33") (pinfunction "PIN33_PIN33") (pintype "bidirectional"))
      (node (ref "U$1") (pin "PIN39") (pinfunction "PIN39_PIN39") (pintype "bidirectional"))
      (node (ref "U$1") (pin "PIN45") (pinfunction "PIN45_PIN45") (pintype "bidirectional"))
      (node (ref "U$1") (pin "PIN8") (pinfunction "PIN8_PIN8") (pintype "bidirectional"))
      (node (ref "U$2") (pin "PIN14") (pinfunction "PIN14_PIN14") (pintype "bidirectional"))
      (node (ref "U$2") (pin "PIN20") (pinfunction "PIN20_PIN20") (pintype "bidirectional"))
      (node (ref "U$2") (pin "PIN33") (pinfunction "PIN33_PIN33") (pintype "bidirectional"))
      (node (ref "U$2") (pin "PIN39") (pinfunction "PIN39_PIN39") (pintype "bidirectional"))
      (node (ref "U$2") (pin "PIN45") (pinfunction "PIN45_PIN45") (pintype "bidirectional"))
      (node (ref "U$2") (pin "PIN8") (pinfunction "PIN8_PIN8") (pintype "bidirectional"))
      (node (ref "U$3") (pin "PIN14") (pinfunction "PIN14_PIN14") (pintype "bidirectional"))
      (node (ref "U$3") (pin "PIN20") (pinfunction "PIN20_PIN20") (pintype "bidirectional"))
      (node (ref "U$3") (pin "PIN33") (pinfunction "PIN33_PIN33") (pintype "bidirectional"))
      (node (ref "U$3") (pin "PIN39") (pinfunction "PIN39_PIN39") (pintype "bidirectional"))
      (node (ref "U$3") (pin "PIN45") (pinfunction "PIN45_PIN45") (pintype "bidirectional"))
      (node (ref "U$3") (pin "PIN8") (pinfunction "PIN8_PIN8") (pintype "bidirectional"))
      (node (ref "U$4") (pin "PIN14") (pinfunction "PIN14_PIN14") (pintype "bidirectional"))
      (node (ref "U$4") (pin "PIN20") (pinfunction "PIN20_PIN20") (pintype "bidirectional"))
      (node (ref "U$4") (pin "PIN33") (pinfunction "PIN33_PIN33") (pintype "bidirectional"))
      (node (ref "U$4") (pin "PIN39") (pinfunction "PIN39_PIN39") (pintype "bidirectional"))
      (node (ref "U$4") (pin "PIN45") (pinfunction "PIN45_PIN45") (pintype "bidirectional"))
      (node (ref "U$4") (pin "PIN8") (pinfunction "PIN8_PIN8") (pintype "bidirectional"))
      (node (ref "U$5") (pin "PIN14") (pinfunction "PIN14_PIN14") (pintype "bidirectional"))
      (node (ref "U$5") (pin "PIN20") (pinfunction "PIN20_PIN20") (pintype "bidirectional"))
      (node (ref "U$5") (pin "PIN33") (pinfunction "PIN33_PIN33") (pintype "bidirectional"))
      (node (ref "U$5") (pin "PIN39") (pinfunction "PIN39_PIN39") (pintype "bidirectional"))
      (node (ref "U$5") (pin "PIN45") (pinfunction "PIN45_PIN45") (pintype "bidirectional"))
      (node (ref "U$5") (pin "PIN8") (pinfunction "PIN8_PIN8") (pintype "bidirectional"))
      (node (ref "U$6") (pin "PIN14") (pinfunction "PIN14_PIN14") (pintype "bidirectional"))
      (node (ref "U$6") (pin "PIN20") (pinfunction "PIN20_PIN20") (pintype "bidirectional"))
      (node (ref "U$6") (pin "PIN33") (pinfunction "PIN33_PIN33") (pintype "bidirectional"))
      (node (ref "U$6") (pin "PIN39") (pinfunction "PIN39_PIN39") (pintype "bidirectional"))
      (node (ref "U$6") (pin "PIN45") (pinfunction "PIN45_PIN45") (pintype "bidirectional"))
      (node (ref "U$6") (pin "PIN8") (pinfunction "PIN8_PIN8") (pintype "bidirectional"))
    )
    (net (code "46") (name "unconnected-(D1-PadA)") (class "Default")
      (node (ref "D1") (pin "A") (pinfunction "A_A") (pintype "passive"))
    )
    (net (code "47") (name "unconnected-(D1-PadC)") (class "Default")
      (node (ref "D1") (pin "C") (pinfunction "C_C") (pintype "passive"))
    )
    (net (code "48") (name "unconnected-(D2-PadA)") (class "Default")
      (node (ref "D2") (pin "A") (pinfunction "A_A") (pintype "passive"))
    )
    (net (code "49") (name "unconnected-(D2-PadC)") (class "Default")
      (node (ref "D2") (pin "C") (pinfunction "C_C") (pintype "passive"))
    )
    (net (code "50") (name "unconnected-(D3-PadA)") (class "Default")
      (node (ref "D3") (pin "A") (pinfunction "A_A") (pintype "passive"))
    )
    (net (code "51") (name "unconnected-(D3-PadC)") (class "Default")
      (node (ref "D3") (pin "C") (pinfunction "C_C") (pintype "passive"))
    )
    (net (code "52") (name "unconnected-(D4-PadA)") (class "Default")
      (node (ref "D4") (pin "A") (pinfunction "A_A") (pintype "passive"))
    )
    (net (code "53") (name "unconnected-(D4-PadC)") (class "Default")
      (node (ref "D4") (pin "C") (pinfunction "C_C") (pintype "passive"))
    )
    (net (code "54") (name "unconnected-(D5-PadA)") (class "Default")
      (node (ref "D5") (pin "A") (pinfunction "A_A") (pintype "passive"))
    )
    (net (code "55") (name "unconnected-(D5-PadC)") (class "Default")
      (node (ref "D5") (pin "C") (pinfunction "C_C") (pintype "passive"))
    )
    (net (code "56") (name "unconnected-(D6-PadA)") (class "Default")
      (node (ref "D6") (pin "A") (pinfunction "A_A") (pintype "passive"))
    )
    (net (code "57") (name "unconnected-(D6-PadC)") (class "Default")
      (node (ref "D6") (pin "C") (pinfunction "C_C") (pintype "passive"))
    )
    (net (code "58") (name "unconnected-(D7-PadA)") (class "Default")
      (node (ref "D7") (pin "A") (pinfunction "A_A") (pintype "passive"))
    )
    (net (code "59") (name "unconnected-(D7-PadC)") (class "Default")
      (node (ref "D7") (pin "C") (pinfunction "C_C") (pintype "passive"))
    )
    (net (code "60") (name "unconnected-(D8-PadA)") (class "Default")
      (node (ref "D8") (pin "A") (pinfunction "A_A") (pintype "passive"))
    )
    (net (code "61") (name "unconnected-(D8-PadC)") (class "Default")
      (node (ref "D8") (pin "C") (pinfunction "C_C") (pintype "passive"))
    )
    (net (code "62") (name "unconnected-(D9-PadA)") (class "Default")
      (node (ref "D9") (pin "A") (pinfunction "A_A") (pintype "passive"))
    )
    (net (code "63") (name "unconnected-(D9-PadC)") (class "Default")
      (node (ref "D9") (pin "C") (pinfunction "C_C") (pintype "passive"))
    )
    (net (code "64") (name "unconnected-(D10-PadA)") (class "Default")
      (node (ref "D10") (pin "A") (pinfunction "A_A") (pintype "passive"))
    )
    (net (code "65") (name "unconnected-(D10-PadC)") (class "Default")
      (node (ref "D10") (pin "C") (pinfunction "C_C") (pintype "passive"))
    )
    (net (code "66") (name "unconnected-(D11-PadA)") (class "Default")
      (node (ref "D11") (pin "A") (pinfunction "A_A") (pintype "passive"))
    )
    (net (code "67") (name "unconnected-(D11-PadC)") (class "Default")
      (node (ref "D11") (pin "C") (pinfunction "C_C") (pintype "passive"))
    )
    (net (code "68") (name "unconnected-(D12-PadA)") (class "Default")
      (node (ref "D12") (pin "A") (pinfunction "A_A") (pintype "passive"))
    )
    (net (code "69") (name "unconnected-(D12-PadC)") (class "Default")
      (node (ref "D12") (pin "C") (pinfunction "C_C") (pintype "passive"))
    )
    (net (code "70") (name "unconnected-(D13-PadA)") (class "Default")
      (node (ref "D13") (pin "A") (pinfunction "A_A") (pintype "passive"))
    )
    (net (code "71") (name "unconnected-(D13-PadC)") (class "Default")
      (node (ref "D13") (pin "C") (pinfunction "C_C") (pintype "passive"))
    )
    (net (code "72") (name "unconnected-(D14-PadA)") (class "Default")
      (node (ref "D14") (pin "A") (pinfunction "A_A") (pintype "passive"))
    )
    (net (code "73") (name "unconnected-(D14-PadC)") (class "Default")
      (node (ref "D14") (pin "C") (pinfunction "C_C") (pintype "passive"))
    )
    (net (code "74") (name "unconnected-(D15-PadA)") (class "Default")
      (node (ref "D15") (pin "A") (pinfunction "A_A") (pintype "passive"))
    )
    (net (code "75") (name "unconnected-(D15-PadC)") (class "Default")
      (node (ref "D15") (pin "C") (pinfunction "C_C") (pintype "passive"))
    )
    (net (code "76") (name "unconnected-(D16-PadA)") (class "Default")
      (node (ref "D16") (pin "A") (pinfunction "A_A") (pintype "passive"))
    )
    (net (code "77") (name "unconnected-(D16-PadC)") (class "Default")
      (node (ref "D16") (pin "C") (pinfunction "C_C") (pintype "passive"))
    )
    (net (code "78") (name "unconnected-(D17-PadA)") (class "Default")
      (node (ref "D17") (pin "A") (pinfunction "A_A") (pintype "passive"))
    )
    (net (code "79") (name "unconnected-(D17-PadC)") (class "Default")
      (node (ref "D17") (pin "C") (pinfunction "C_C") (pintype "passive"))
    )
    (net (code "80") (name "unconnected-(D18-PadA)") (class "Default")
      (node (ref "D18") (pin "A") (pinfunction "A_A") (pintype "passive"))
    )
    (net (code "81") (name "unconnected-(D18-PadC)") (class "Default")
      (node (ref "D18") (pin "C") (pinfunction "C_C") (pintype "passive"))
    )
    (net (code "82") (name "unconnected-(U$1-PadPIN6)") (class "Default")
      (node (ref "U$1") (pin "PIN6") (pinfunction "PIN6_PIN6") (pintype "bidirectional"))
    )
    (net (code "83") (name "unconnected-(U$1-PadPIN7)") (class "Default")
      (node (ref "U$1") (pin "PIN7") (pinfunction "PIN7_PIN7") (pintype "bidirectional"))
    )
    (net (code "84") (name "unconnected-(U$1-PadPIN31)") (class "Default")
      (node (ref "U$1") (pin "PIN31") (pinfunction "PIN31_PIN31") (pintype "bidirectional"))
    )
    (net (code "85") (name "unconnected-(U$1-PadPIN32)") (class "Default")
      (node (ref "U$1") (pin "PIN32") (pinfunction "PIN32_PIN32") (pintype "bidirectional"))
    )
    (net (code "86") (name "unconnected-(U$2-PadPIN6)") (class "Default")
      (node (ref "U$2") (pin "PIN6") (pinfunction "PIN6_PIN6") (pintype "bidirectional"))
    )
    (net (code "87") (name "unconnected-(U$2-PadPIN7)") (class "Default")
      (node (ref "U$2") (pin "PIN7") (pinfunction "PIN7_PIN7") (pintype "bidirectional"))
    )
    (net (code "88") (name "unconnected-(U$2-PadPIN31)") (class "Default")
      (node (ref "U$2") (pin "PIN31") (pinfunction "PIN31_PIN31") (pintype "bidirectional"))
    )
    (net (code "89") (name "unconnected-(U$2-PadPIN32)") (class "Default")
      (node (ref "U$2") (pin "PIN32") (pinfunction "PIN32_PIN32") (pintype "bidirectional"))
    )
    (net (code "90") (name "unconnected-(U$3-PadPIN6)") (class "Default")
      (node (ref "U$3") (pin "PIN6") (pinfunction "PIN6_PIN6") (pintype "bidirectional"))
    )
    (net (code "91") (name "unconnected-(U$3-PadPIN7)") (class "Default")
      (node (ref "U$3") (pin "PIN7") (pinfunction "PIN7_PIN7") (pintype "bidirectional"))
    )
    (net (code "92") (name "unconnected-(U$3-PadPIN31)") (class "Default")
      (node (ref "U$3") (pin "PIN31") (pinfunction "PIN31_PIN31") (pintype "bidirectional"))
    )
    (net (code "93") (name "unconnected-(U$3-PadPIN32)") (class "Default")
      (node (ref "U$3") (pin "PIN32") (pinfunction "PIN32_PIN32") (pintype "bidirectional"))
    )
    (net (code "94") (name "unconnected-(U$4-PadPIN6)") (class "Default")
      (node (ref "U$4") (pin "PIN6") (pinfunction "PIN6_PIN6") (pintype "bidirectional"))
    )
    (net (code "95") (name "unconnected-(U$4-PadPIN7)") (class "Default")
      (node (ref "U$4") (pin "PIN7") (pinfunction "PIN7_PIN7") (pintype "bidirectional"))
    )
    (net (code "96") (name "unconnected-(U$4-PadPIN31)") (class "Default")
      (node (ref "U$4") (pin "PIN31") (pinfunction "PIN31_PIN31") (pintype "bidirectional"))
    )
    (net (code "97") (name "unconnected-(U$4-PadPIN32)") (class "Default")
      (node (ref "U$4") (pin "PIN32") (pinfunction "PIN32_PIN32") (pintype "bidirectional"))
    )
    (net (code "98") (name "unconnected-(U$5-PadPIN32)") (class "Default")
      (node (ref "U$5") (pin "PIN32") (pinfunction "PIN32_PIN32") (pintype "bidirectional"))
    )
    (net (code "99") (name "unconnected-(U$6-PadPIN6)") (class "Default")
      (node (ref "U$6") (pin "PIN6") (pinfunction "PIN6_PIN6") (pintype "bidirectional"))
    )
    (net (code "100") (name "unconnected-(U$6-PadPIN7)") (class "Default")
      (node (ref "U$6") (pin "PIN7") (pinfunction "PIN7_PIN7") (pintype "bidirectional"))
    )
    (net (code "101") (name "unconnected-(U$6-PadPIN31)") (class "Default")
      (node (ref "U$6") (pin "PIN31") (pinfunction "PIN31_PIN31") (pintype "bidirectional"))
    )
    (net (code "102") (name "unconnected-(U$6-PadPIN32)") (class "Default")
      (node (ref "U$6") (pin "PIN32") (pinfunction "PIN32_PIN32") (pintype "bidirectional"))
    )
  )
)
